# 0002_Page_2.net
KiCad netlist of a schematic drawn in Altium Designer
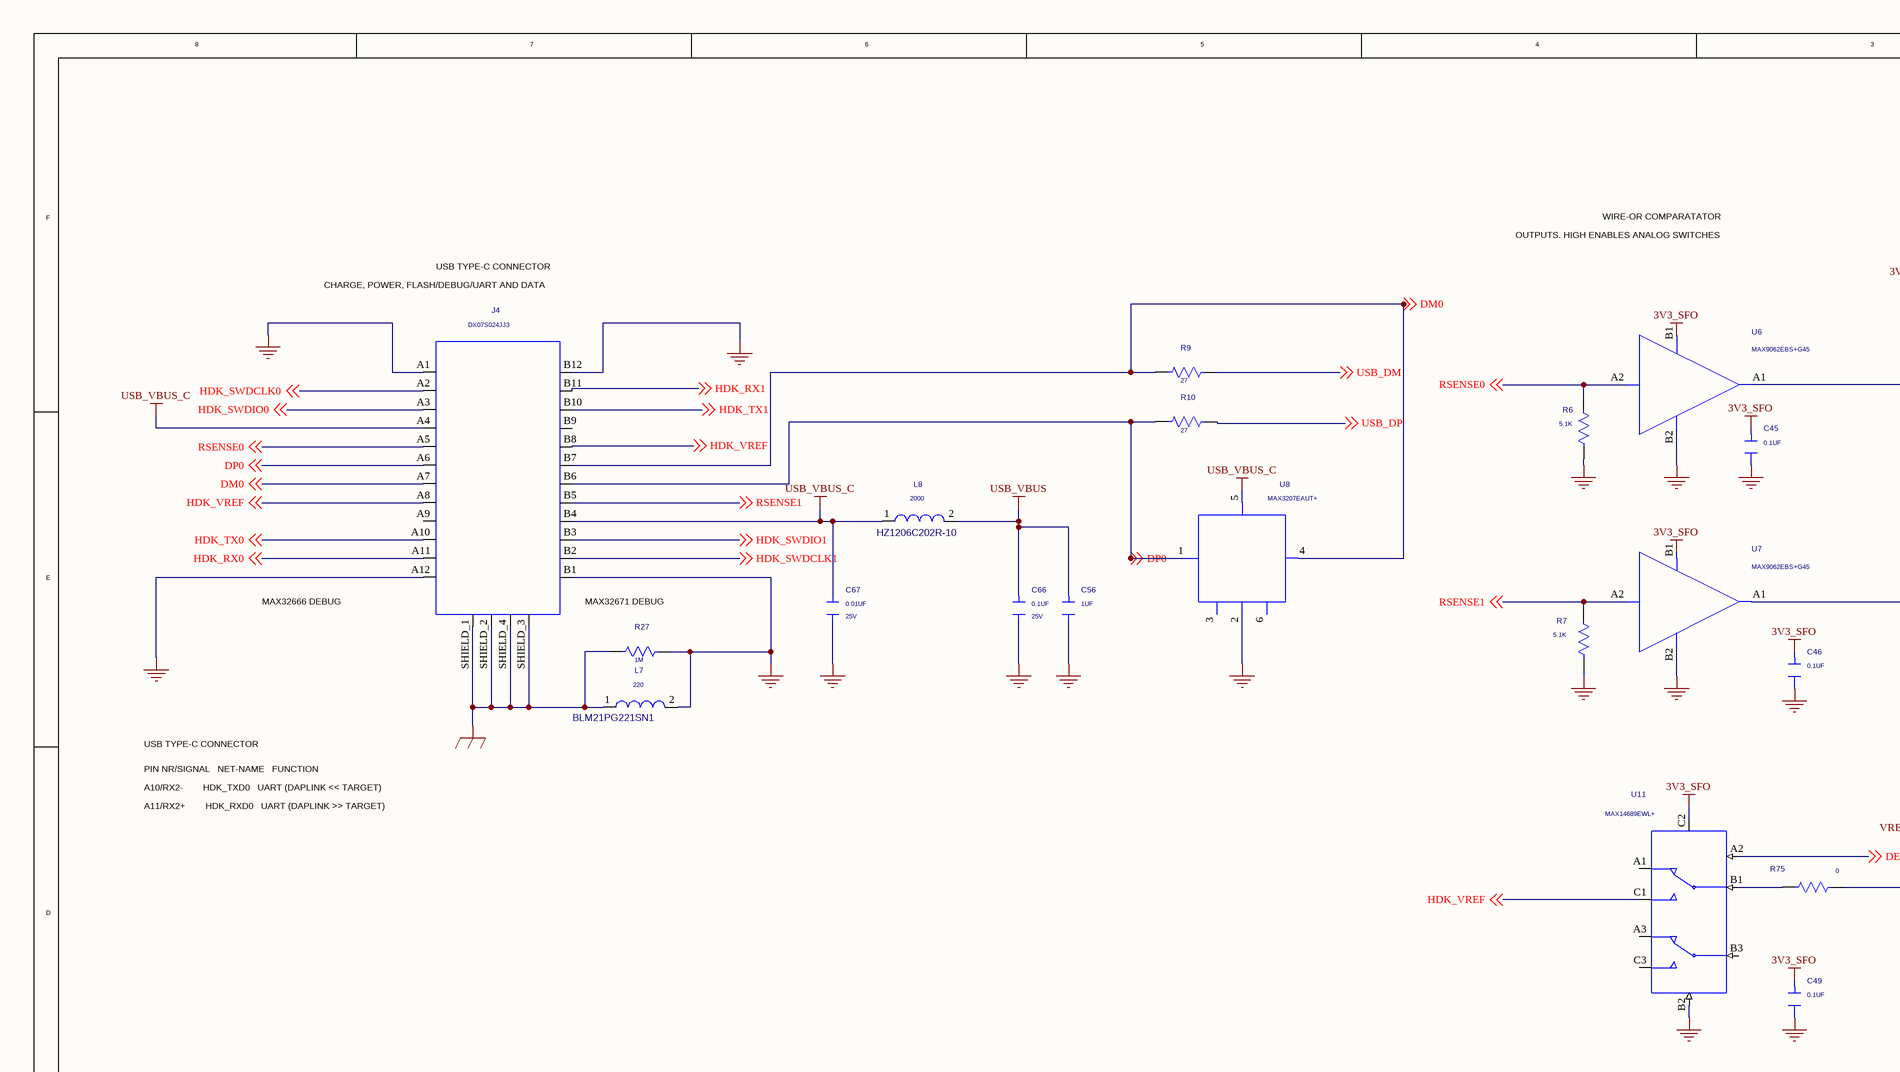
[diagram p0: 0002_Page 2.SchDoc, top left]
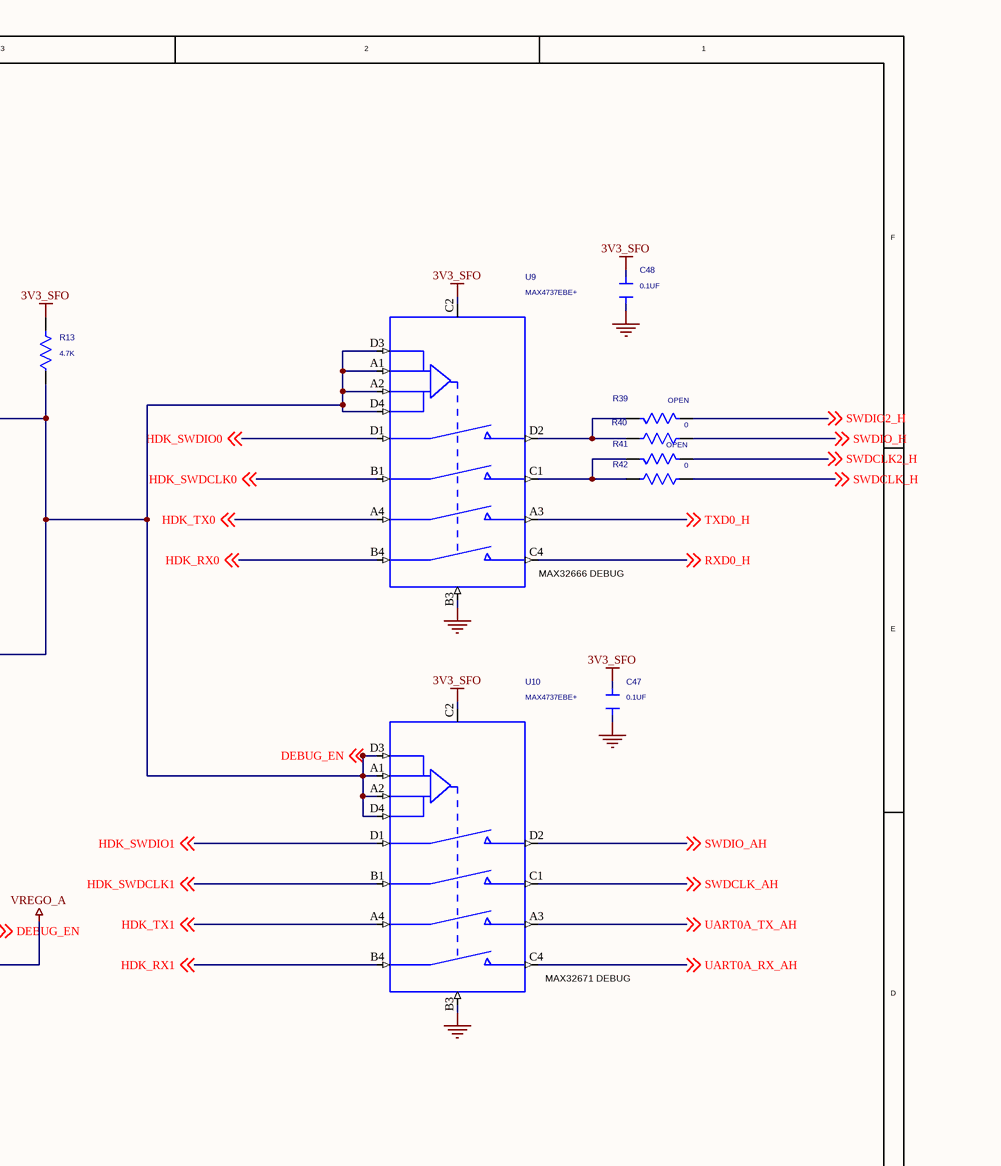
[diagram p1: 0002_Page 2.SchDoc, top middle]
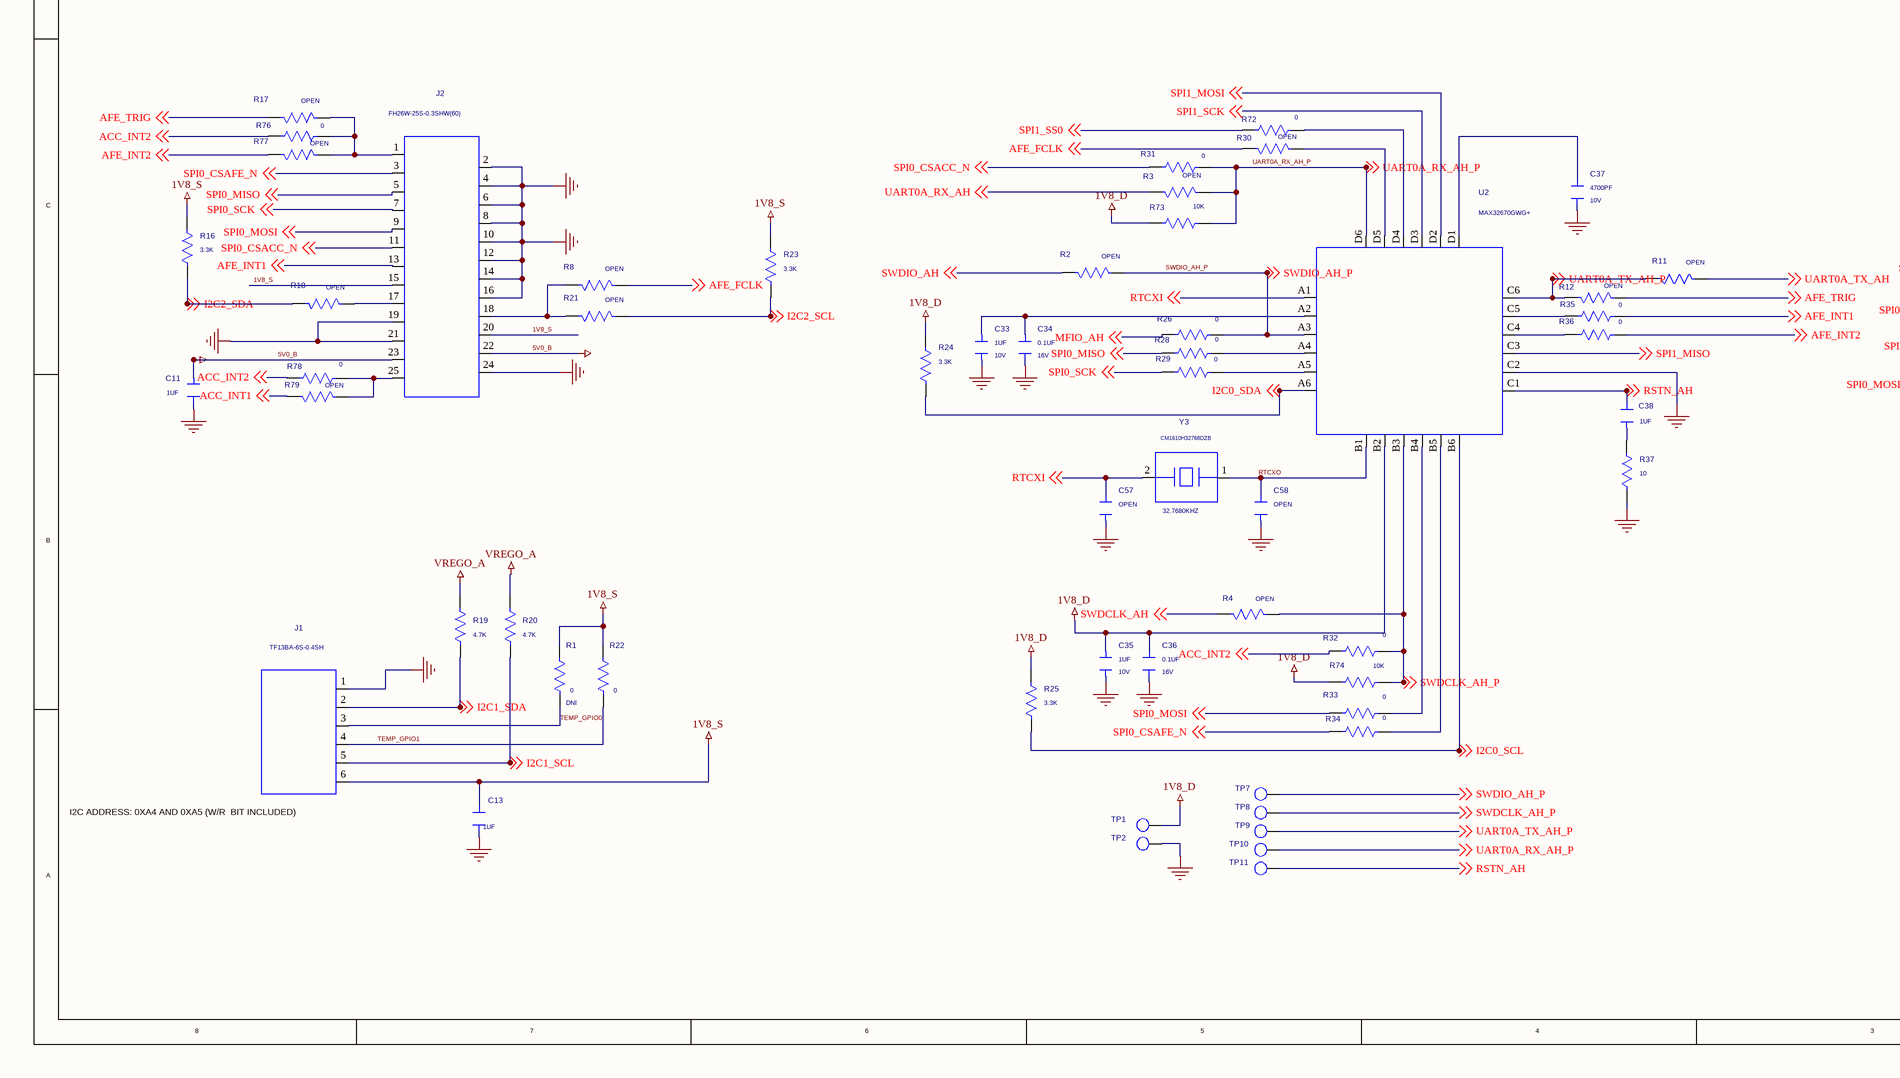
[diagram p2: 0002_Page 2.SchDoc, bottom left]
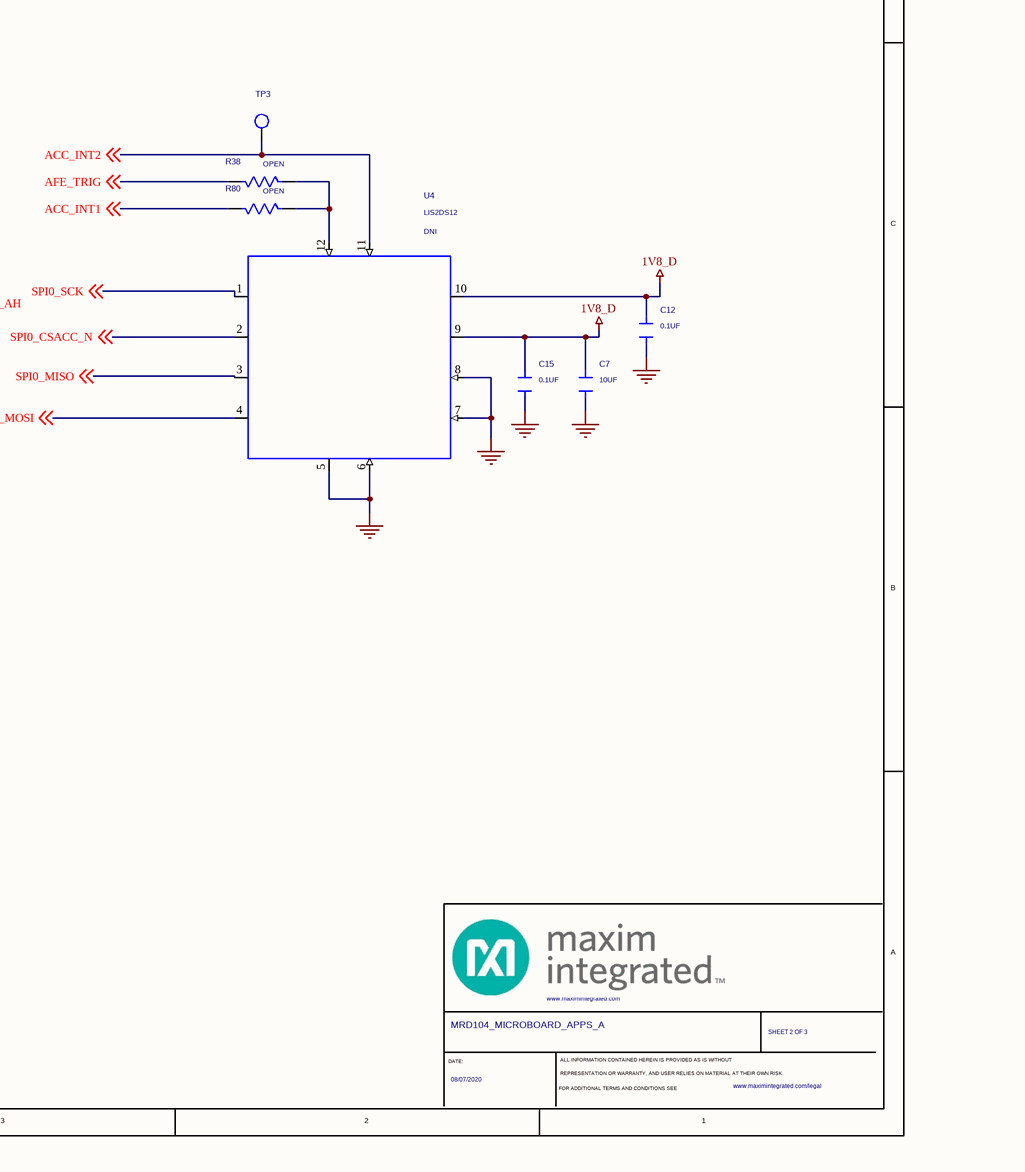
[diagram p3: 0002_Page 2.SchDoc, bottom middle]
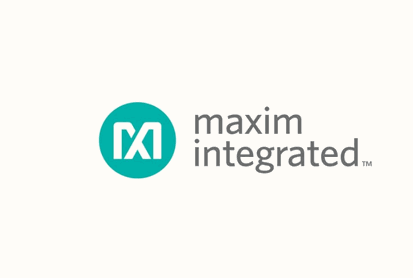
[diagram p4: 0002_Page 2.SchDoc, bottom right]

(export (version "E")
  (design (tool "Eeschema 10.0.6"))
  (components
    (comp (ref "C7")
      (value "10UF")
      (footprint "0603")
      (description "CAP; SMT (0603); 10UF; 20%; 25V; X5R; CERAMIC")
      (fields
        (field (name "MFG_PART_NUMBER") "C1608X5R1E106M080AC;CL10A106MA8NRNC;GRM188R61E106MA73;ZRB18AR61E106ME01;GRT188R61E106ME13")
        (field (name "TOLERANCE") "20%")
      )
      (libsource (lib "*") (part "CAP_NP"))
    )
    (comp (ref "C11")
      (value "1UF")
      (footprint "CAPC0603X33M")
      (description "CAP; SMT (0201); 1UF; 20%; 10V; X5R; CERAMIC")
      (fields (field (name "MFG_PART_NUMBER") "GRM033R61A105ME15") (field (name "TOLERANCE") "20%"))
      (libsource (lib "*") (part "CAP_NP#1"))
    )
    (comp (ref "C12")
      (value "0.1UF")
      (footprint "CAPC0603X33M")
      (description "CAP; SMT (0201); 0.1UF; 10%; 16V; X7S; CERAMIC")
      (fields (field (name "MFG_PART_NUMBER") "GRM033C71C104KE14") (field (name "TOLERANCE") "10%"))
      (libsource (lib "*") (part "CAP_NP"))
    )
    (comp (ref "C13")
      (value "1UF")
      (footprint "CAPC0603X33M")
      (description "CAP; SMT (0201); 1UF; 20%; 10V; X5R; CERAMIC")
      (fields (field (name "MFG_PART_NUMBER") "GRM033R61A105ME15") (field (name "TOLERANCE") "20%"))
      (libsource (lib "*") (part "CAP_NP#1"))
    )
    (comp (ref "C15")
      (value "0.1UF")
      (footprint "CAPC0603X33M")
      (description "CAP; SMT (0201); 0.1UF; 10%; 16V; X7S; CERAMIC")
      (fields (field (name "MFG_PART_NUMBER") "GRM033C71C104KE14") (field (name "TOLERANCE") "10%"))
      (libsource (lib "*") (part "CAP_NP"))
    )
    (comp (ref "C33")
      (value "1UF")
      (footprint "CAPC0603X33M")
      (description "CAP; SMT (0201); 1UF; 20%; 10V; X6S; CERAMIC")
      (fields
        (field (name "MFG_PART_NUMBER") "GRM033C81A105ME05")
        (field (name "TOLERANCE") "20%")
        (field (name "VOLTAGE_RATING") "10V")
      )
      (libsource (lib "*") (part "CAP_NP"))
    )
    (comp (ref "C34")
      (value "0.1UF")
      (footprint "CAPC0603X33M")
      (description "CAP; SMT (0201); 0.1UF; 10%; 16V; X7S; CERAMIC")
      (fields
        (field (name "MFG_PART_NUMBER") "GRM033C71C104KE14")
        (field (name "TOLERANCE") "10%")
        (field (name "VOLTAGE_RATING") "16V")
      )
      (libsource (lib "*") (part "CAP_NP"))
    )
    (comp (ref "C35")
      (value "1UF")
      (footprint "CAPC0603X33M")
      (description "CAP; SMT (0201); 1UF; 20%; 10V; X6S; CERAMIC")
      (fields
        (field (name "MFG_PART_NUMBER") "GRM033C81A105ME05")
        (field (name "TOLERANCE") "20%")
        (field (name "VOLTAGE_RATING") "10V")
      )
      (libsource (lib "*") (part "CAP_NP"))
    )
    (comp (ref "C36")
      (value "0.1UF")
      (footprint "CAPC0603X33M")
      (description "CAP; SMT (0201); 0.1UF; 10%; 16V; X7S; CERAMIC")
      (fields
        (field (name "MFG_PART_NUMBER") "GRM033C71C104KE14")
        (field (name "TOLERANCE") "10%")
        (field (name "VOLTAGE_RATING") "16V")
      )
      (libsource (lib "*") (part "CAP_NP"))
    )
    (comp (ref "C37")
      (value "4700PF")
      (footprint "CAPC0603X33M")
      (description "CAP; SMT (0201); 4700PF; 10%; 10V; X7R; CERAMIC")
      (fields
        (field (name "MFG_PART_NUMBER") "GRM033R71A472KA01D")
        (field (name "TOLERANCE") "10%")
        (field (name "VOLTAGE_RATING") "10V")
      )
      (libsource (lib "*") (part "CAP_NP"))
    )
    (comp (ref "C38")
      (value "1UF")
      (footprint "CAPC0603X33M")
      (description "CAP; SMT (0201); 1UF; 20%; 10V; X6S; CERAMIC")
      (fields (field (name "MFG_PART_NUMBER") "GRM033C81A105ME05") (field (name "TOLERANCE") "20%"))
      (libsource (lib "*") (part "CAP_NP"))
    )
    (comp (ref "C45")
      (value "0.1UF")
      (footprint "CAPC0603X33M")
      (description "CAP; SMT (0201); 0.1UF; 10%; 16V; X5R; CERAMIC")
      (fields
        (field (name "MFG_PART_NUMBER") "GRM033R61C104K;C0603X5R1C104K030BC")
        (field (name "TOLERANCE") "10%")
      )
      (libsource (lib "*") (part "CAP_NP"))
    )
    (comp (ref "C46")
      (value "0.1UF")
      (footprint "CAPC0603X33M")
      (description "CAP; SMT (0201); 0.1UF; 10%; 16V; X5R; CERAMIC")
      (fields
        (field (name "MFG_PART_NUMBER") "GRM033R61C104K;C0603X5R1C104K030BC")
        (field (name "TOLERANCE") "10%")
      )
      (libsource (lib "*") (part "CAP_NP"))
    )
    (comp (ref "C47")
      (value "0.1UF")
      (footprint "CAPC0603X33M")
      (description "CAP; SMT (0201); 0.1UF; 10%; 16V; X5R; CERAMIC")
      (fields
        (field (name "MFG_PART_NUMBER") "GRM033R61C104K;C0603X5R1C104K030BC")
        (field (name "TOLERANCE") "10%")
      )
      (libsource (lib "*") (part "CAP_NP"))
    )
    (comp (ref "C48")
      (value "0.1UF")
      (footprint "CAPC0603X33M")
      (description "CAP; SMT (0201); 0.1UF; 10%; 16V; X5R; CERAMIC")
      (fields
        (field (name "MFG_PART_NUMBER") "GRM033R61C104K;C0603X5R1C104K030BC")
        (field (name "TOLERANCE") "10%")
      )
      (libsource (lib "*") (part "CAP_NP"))
    )
    (comp (ref "C49")
      (value "0.1UF")
      (footprint "CAPC0603X33M")
      (description "CAP; SMT (0201); 0.1UF; 10%; 16V; X5R; CERAMIC")
      (fields
        (field (name "MFG_PART_NUMBER") "GRM033R61C104K;C0603X5R1C104K030BC")
        (field (name "TOLERANCE") "10%")
      )
      (libsource (lib "*") (part "CAP_NP"))
    )
    (comp (ref "C56")
      (value "1UF")
      (footprint "0402")
      (description "CAP; SMT (0402); 1UF; 10%; 35V; X5R;  CERAMIC")
      (fields (field (name "MFG_PART_NUMBER") "C1005X5R1V105K050BC") (field (name "TOLERANCE") "10%"))
      (libsource (lib "*") (part "CAP_NP"))
    )
    (comp (ref "C57")
      (value "OPEN")
      (footprint "CAPC0603X23L")
      (description "CAPACITOR; SMT (0201); OPEN; FORMFACTOR")
      (libsource (lib "*") (part "EK_CAP_NP"))
    )
    (comp (ref "C58")
      (value "OPEN")
      (footprint "CAPC0603X23L")
      (description "CAPACITOR; SMT (0201); OPEN; FORMFACTOR")
      (libsource (lib "*") (part "EK_CAP_NP"))
    )
    (comp (ref "C66")
      (value "0.1UF")
      (footprint "CAPC0603X33M")
      (description "CAP; SMT (0201); 0.1UF; 20%; 25V; X5R; CERAMIC")
      (fields
        (field (name "MFG_PART_NUMBER") "C0603X5R1E104M030BB;GRM033R61E104ME14")
        (field (name "TOLERANCE") "20%")
        (field (name "VOLTAGE_RATING") "25V")
      )
      (libsource (lib "*") (part "CAP_NP"))
    )
    (comp (ref "C67")
      (value "0.01UF")
      (footprint "0402")
      (description "CAP; SMT (0402); 0.01UF; 10%; 25V; X5R; CERAMIC")
      (fields
        (field (name "MFG_PART_NUMBER") "04023D103KAT2A")
        (field (name "TOLERANCE") "10%")
        (field (name "VOLTAGE_RATING") "25V")
      )
      (libsource (lib "*") (part "CAP_NP"))
    )
    (comp (ref "J1")
      (value "TF13BA-6S-0.4SH")
      (footprint "HRSC_TF13BA-6S-0_4SH")
      (description "CONNECTOR; FEMALE; SMT; TF13BA SERIES; FPC/FFC CONNECTOR; 6PINS")
      (fields (field (name "MANUFACTURER") "HIROSE ELECTRIC CO LTD"))
      (libsource (lib "*") (part "TF13BA-6S"))
    )
    (comp (ref "J2")
      (value "FH26W-25S-0.3SHW(60)")
      (footprint "HRSC_FH26W-25S-0_3SHW")
      (description "CONNECTOR; FEMALE; SMT; FPC CONNECTOR; RIGHT ANGLE; 25PINS")
      (fields (field (name "MANUFACTURER") "HIROSE ELECTRIC CO. LTD."))
      (libsource (lib "*") (part "FH26-25S"))
    )
    (comp (ref "J4")
      (value "DX07S024JJ3")
      (footprint "JAE_DX07S024JJ3")
      (description "CONNECTOR; FEMALE; SMT; USB TYPE-C CONNECTOR; DX07 SERIES RECEPTACLE; RIGHT ANGLE; 24PINS")
      (fields
        (field (name "MFG_PART_NUMBER") "DX07S024JJ3R1300")
        (field (name "MANUFACTURER") "JAE ELECTRONIC INDUSTRY")
      )
      (libsource (lib "*") (part "DX07S024JJ3"))
    )
    (comp (ref "L7")
      (value "220")
      (footprint "0805")
      (description "INDUCTOR; SMT (0805); FERRITE-BEAD; 220; TOL=+/-25%; 0.2A")
      (fields
        (field (name "MFG_PART_NUMBER") "BLM21PG221SN1")
        (field (name "TOLERANCE") "25%")
        (field (name "MANUFACTURER") "MURATA")
      )
      (libsource (lib "*") (part "FERRITEBEAD"))
    )
    (comp (ref "L8")
      (value "2000")
      (footprint "1206")
      (description "INDUCTOR; SMT (1206); FERRITE-BEAD; 2000; TOL=+/-25%; 0.3A")
      (fields
        (field (name "MFG_PART_NUMBER") "HZ1206C202R-10")
        (field (name "TOLERANCE") "25%")
        (field (name "MANUFACTURER") "LAIRD TECHNOLOGIES")
      )
      (libsource (lib "*") (part "FERRITEBEAD"))
    )
    (comp (ref "R1")
      (value "0")
      (footprint "RESC0603X33M")
      (description "RES; SMT (0201); 0; 1%; JUMPER; 0.0500W")
      (fields
        (field (name "TOLERANCE") "1%")
        (field (name "VARIANT") "DNI")
        (field (name "MANUFACTURER") "VISHAY DALE;PANASONIC")
      )
      (libsource (lib "*") (part "RES_SMD"))
    )
    (comp (ref "R2")
      (value "OPEN")
      (footprint "RESC0603X23L")
      (description "RESISTOR; 0201; OPEN; FORMFACTOR")
      (libsource (lib "*") (part "EK_RES_SMD"))
    )
    (comp (ref "R3")
      (value "OPEN")
      (footprint "RESC0603X23L")
      (description "RESISTOR; 0201; OPEN; FORMFACTOR")
      (libsource (lib "*") (part "EK_RES_SMD"))
    )
    (comp (ref "R4")
      (value "OPEN")
      (footprint "RESC0603X23L")
      (description "RESISTOR; 0201; OPEN; FORMFACTOR")
      (libsource (lib "*") (part "EK_RES_SMD"))
    )
    (comp (ref "R6")
      (value "5.1K")
      (footprint "RESC0603X33M")
      (description "RES; SMT (0201); 5.1K; 1%; +/-200PPM/DEGC; 0.0500W")
      (fields (field (name "MFG_PART_NUMBER") "ERJ-1GNF5101C") (field (name "TOLERANCE") "1%"))
      (libsource (lib "*") (part "RES_SMD"))
    )
    (comp (ref "R7")
      (value "5.1K")
      (footprint "RESC0603X33M")
      (description "RES; SMT (0201); 5.1K; 1%; +/-200PPM/DEGC; 0.0500W")
      (fields (field (name "MFG_PART_NUMBER") "ERJ-1GNF5101C") (field (name "TOLERANCE") "1%"))
      (libsource (lib "*") (part "RES_SMD"))
    )
    (comp (ref "R8")
      (value "OPEN")
      (footprint "RESC0603X23L")
      (description "RESISTOR; 0201; OPEN; FORMFACTOR")
      (libsource (lib "*") (part "EK_RES_SMD"))
    )
    (comp (ref "R9")
      (value "27")
      (footprint "RESC0603X33M")
      (description "RES; SMT (0201); 27; 1%; +/-100PPM/DEGC; 0.0500W")
      (fields (field (name "MFG_PART_NUMBER") "ERJ-1GEF27R0C") (field (name "TOLERANCE") "1%"))
      (libsource (lib "*") (part "RES_SMD"))
    )
    (comp (ref "R10")
      (value "27")
      (footprint "RESC0603X33M")
      (description "RES; SMT (0201); 27; 1%; +/-100PPM/DEGC; 0.0500W")
      (fields (field (name "MFG_PART_NUMBER") "ERJ-1GEF27R0C") (field (name "TOLERANCE") "1%"))
      (libsource (lib "*") (part "RES_SMD"))
    )
    (comp (ref "R11")
      (value "OPEN")
      (footprint "RESC0603X23L")
      (description "RESISTOR; 0201; OPEN; FORMFACTOR")
      (libsource (lib "*") (part "EK_RES_SMD"))
    )
    (comp (ref "R12")
      (value "OPEN")
      (footprint "RESC0603X23L")
      (description "RESISTOR; 0201; OPEN; FORMFACTOR")
      (libsource (lib "*") (part "EK_RES_SMD"))
    )
    (comp (ref "R13")
      (value "4.7K")
      (footprint "RESC0603X26M")
      (description "RES; SMT (0201); 4.7K; 1%; +/-200PPM/DEGC; 0.0500W")
      (fields (field (name "MFG_PART_NUMBER") "ERJ-1GNF4701") (field (name "TOLERANCE") "1%"))
      (libsource (lib "*") (part "RES_SMD#1"))
    )
    (comp (ref "R16")
      (value "3.3K")
      (footprint "RESC0603X33M")
      (description "RES; SMT (0201); 3.3K; 1%; +/-100PPM/DEGC; 0.0500W")
      (fields (field (name "MFG_PART_NUMBER") "ERJ-1GEF3301C") (field (name "TOLERANCE") "1%"))
      (libsource (lib "*") (part "RES_SMD"))
    )
    (comp (ref "R17")
      (value "OPEN")
      (footprint "RESC0603X23L")
      (description "RESISTOR; 0201; OPEN; FORMFACTOR")
      (libsource (lib "*") (part "EK_RES_SMD"))
    )
    (comp (ref "R18")
      (value "OPEN")
      (footprint "RESC0603X23L")
      (description "RESISTOR; 0201; OPEN; FORMFACTOR")
      (libsource (lib "*") (part "EK_RES_SMD"))
    )
    (comp (ref "R19")
      (value "4.7K")
      (footprint "RESC0603X26M")
      (description "RES; SMT (0201); 4.7K; 1%; +/-200PPM/DEGC; 0.0500W")
      (fields (field (name "MFG_PART_NUMBER") "ERJ-1GNF4701") (field (name "TOLERANCE") "1%"))
      (libsource (lib "*") (part "RES_SMD"))
    )
    (comp (ref "R20")
      (value "4.7K")
      (footprint "RESC0603X26M")
      (description "RES; SMT (0201); 4.7K; 1%; +/-200PPM/DEGC; 0.0500W")
      (fields (field (name "MFG_PART_NUMBER") "ERJ-1GNF4701") (field (name "TOLERANCE") "1%"))
      (libsource (lib "*") (part "RES_SMD"))
    )
    (comp (ref "R21")
      (value "OPEN")
      (footprint "RESC0603X23L")
      (description "RESISTOR; 0201; OPEN; FORMFACTOR")
      (libsource (lib "*") (part "EK_RES_SMD"))
    )
    (comp (ref "R22")
      (value "0")
      (footprint "RESC0603X33M")
      (description "RES; SMT (0201); 0; 1%; JUMPER; 0.0500W")
      (fields (field (name "TOLERANCE") "1%") (field (name "MANUFACTURER") "VISHAY DALE;PANASONIC"))
      (libsource (lib "*") (part "RES_SMD"))
    )
    (comp (ref "R23")
      (value "3.3K")
      (footprint "RESC0603X33M")
      (description "RES; SMT (0201); 3.3K; 1%; +/-100PPM/DEGC; 0.0500W")
      (fields (field (name "MFG_PART_NUMBER") "ERJ-1GEF3301C") (field (name "TOLERANCE") "1%"))
      (libsource (lib "*") (part "RES_SMD"))
    )
    (comp (ref "R24")
      (value "3.3K")
      (footprint "RESC0603X33M")
      (description "RES; SMT (0201); 3.3K; 1%; +/-100PPM/DEGC; 0.0500W")
      (fields (field (name "MFG_PART_NUMBER") "ERJ-1GEF3301C") (field (name "TOLERANCE") "1%"))
      (libsource (lib "*") (part "RES_SMD"))
    )
    (comp (ref "R25")
      (value "3.3K")
      (footprint "RESC0603X33M")
      (description "RES; SMT (0201); 3.3K; 1%; +/-100PPM/DEGC; 0.0500W")
      (fields (field (name "MFG_PART_NUMBER") "ERJ-1GEF3301C") (field (name "TOLERANCE") "1%"))
      (libsource (lib "*") (part "RES_SMD"))
    )
    (comp (ref "R26")
      (value "0")
      (footprint "RESC0603X33M")
      (description "RES; SMT (0201); 0; 1%; JUMPER; 0.0500W")
      (fields (field (name "TOLERANCE") "1%") (field (name "MANUFACTURER") "VISHAY DALE;PANASONIC"))
      (libsource (lib "*") (part "RES_SMD"))
    )
    (comp (ref "R27")
      (value "1M")
      (footprint "0402")
      (description "RES; SMT (0402); 1M; 1%; +/-100PPM/DEGC; 0.1000W")
      (fields (field (name "MFG_PART_NUMBER") "ERJ-2RKF1004") (field (name "TOLERANCE") "1%"))
      (libsource (lib "*") (part "RES_SMD"))
    )
    (comp (ref "R28")
      (value "0")
      (footprint "RESC0603X33M")
      (description "RES; SMT (0201); 0; 1%; JUMPER; 0.0500W")
      (fields (field (name "TOLERANCE") "1%") (field (name "MANUFACTURER") "VISHAY DALE;PANASONIC"))
      (libsource (lib "*") (part "RES_SMD"))
    )
    (comp (ref "R29")
      (value "0")
      (footprint "RESC0603X33M")
      (description "RES; SMT (0201); 0; 1%; JUMPER; 0.0500W")
      (fields (field (name "TOLERANCE") "1%") (field (name "MANUFACTURER") "VISHAY DALE;PANASONIC"))
      (libsource (lib "*") (part "RES_SMD"))
    )
    (comp (ref "R30")
      (value "OPEN")
      (footprint "RESC0603X23L")
      (description "RESISTOR; 0201; OPEN; FORMFACTOR")
      (libsource (lib "*") (part "EK_RES_SMD"))
    )
    (comp (ref "R31")
      (value "0")
      (footprint "RESC0603X33M")
      (description "RES; SMT (0201); 0; 1%; JUMPER; 0.0500W")
      (fields (field (name "TOLERANCE") "1%") (field (name "MANUFACTURER") "VISHAY DALE;PANASONIC"))
      (libsource (lib "*") (part "RES_SMD"))
    )
    (comp (ref "R32")
      (value "0")
      (footprint "RESC0603X33M")
      (description "RES; SMT (0201); 0; 1%; JUMPER; 0.0500W")
      (fields (field (name "TOLERANCE") "1%") (field (name "MANUFACTURER") "VISHAY DALE;PANASONIC"))
      (libsource (lib "*") (part "RES_SMD"))
    )
    (comp (ref "R33")
      (value "0")
      (footprint "RESC0603X33M")
      (description "RES; SMT (0201); 0; 1%; JUMPER; 0.0500W")
      (fields (field (name "TOLERANCE") "1%") (field (name "MANUFACTURER") "VISHAY DALE;PANASONIC"))
      (libsource (lib "*") (part "RES_SMD"))
    )
    (comp (ref "R34")
      (value "0")
      (footprint "RESC0603X33M")
      (description "RES; SMT (0201); 0; 1%; JUMPER; 0.0500W")
      (fields (field (name "TOLERANCE") "1%") (field (name "MANUFACTURER") "VISHAY DALE;PANASONIC"))
      (libsource (lib "*") (part "RES_SMD"))
    )
    (comp (ref "R35")
      (value "0")
      (footprint "RESC0603X33M")
      (description "RES; SMT (0201); 0; 1%; JUMPER; 0.0500W")
      (fields (field (name "TOLERANCE") "1%") (field (name "MANUFACTURER") "VISHAY DALE;PANASONIC"))
      (libsource (lib "*") (part "RES_SMD"))
    )
    (comp (ref "R36")
      (value "0")
      (footprint "RESC0603X33M")
      (description "RES; SMT (0201); 0; 1%; JUMPER; 0.0500W")
      (fields (field (name "TOLERANCE") "1%") (field (name "MANUFACTURER") "VISHAY DALE;PANASONIC"))
      (libsource (lib "*") (part "RES_SMD"))
    )
    (comp (ref "R37")
      (value "10")
      (footprint "RESC0603X33M")
      (description "RES; SMT (0201); 10; 1%; +/-100PPM/DEGC; 0.0500W")
      (fields (field (name "MFG_PART_NUMBER") "ERJ-1GEF10R0") (field (name "TOLERANCE") "1%"))
      (libsource (lib "*") (part "RES_SMD"))
    )
    (comp (ref "R38")
      (value "OPEN")
      (footprint "RESC0603X23L")
      (description "RESISTOR; 0201; OPEN; FORMFACTOR")
      (libsource (lib "*") (part "EK_RES_SMD"))
    )
    (comp (ref "R39")
      (value "OPEN")
      (footprint "RESC0603X23L")
      (description "RESISTOR; 0201; OPEN; FORMFACTOR")
      (libsource (lib "*") (part "EK_RES_SMD"))
    )
    (comp (ref "R40")
      (value "0")
      (footprint "RESC0603X33M")
      (description "RES; SMT (0201); 0; 1%; JUMPER; 0.0500W")
      (fields (field (name "TOLERANCE") "1%") (field (name "MANUFACTURER") "VISHAY DALE;PANASONIC"))
      (libsource (lib "*") (part "RES_SMD"))
    )
    (comp (ref "R41")
      (value "OPEN")
      (footprint "RESC0603X23L")
      (description "RESISTOR; 0201; OPEN; FORMFACTOR")
      (libsource (lib "*") (part "EK_RES_SMD"))
    )
    (comp (ref "R42")
      (value "0")
      (footprint "RESC0603X33M")
      (description "RES; SMT (0201); 0; 1%; JUMPER; 0.0500W")
      (fields (field (name "TOLERANCE") "1%") (field (name "MANUFACTURER") "VISHAY DALE;PANASONIC"))
      (libsource (lib "*") (part "RES_SMD"))
    )
    (comp (ref "R72")
      (value "0")
      (footprint "RESC0603X33M")
      (description "RES; SMT (0201); 0; 1%; JUMPER; 0.0500W")
      (fields (field (name "TOLERANCE") "1%") (field (name "MANUFACTURER") "VISHAY DALE;PANASONIC"))
      (libsource (lib "*") (part "RES_SMD"))
    )
    (comp (ref "R73")
      (value "10K")
      (footprint "RESC0603X33M")
      (description "RES; SMT (0201); 10K; 5%; +/-200PPM/DEGC; 0.0500W")
      (fields (field (name "MFG_PART_NUMBER") "ERJ-1GNJ103") (field (name "TOLERANCE") "5%"))
      (libsource (lib "*") (part "RES_SMD"))
    )
    (comp (ref "R74")
      (value "10K")
      (footprint "RESC0603X33M")
      (description "RES; SMT (0201); 10K; 5%; +/-200PPM/DEGC; 0.0500W")
      (fields (field (name "MFG_PART_NUMBER") "ERJ-1GNJ103") (field (name "TOLERANCE") "5%"))
      (libsource (lib "*") (part "RES_SMD"))
    )
    (comp (ref "R75")
      (value "0")
      (footprint "RESC0603X33M")
      (description "RES; SMT (0201); 0; 1%; JUMPER; 0.0500W")
      (fields (field (name "TOLERANCE") "1%") (field (name "MANUFACTURER") "VISHAY DALE;PANASONIC"))
      (libsource (lib "*") (part "RES_SMD"))
    )
    (comp (ref "R76")
      (value "0")
      (footprint "RESC0603X33M")
      (description "RES; SMT (0201); 0; 1%; JUMPER; 0.0500W")
      (fields (field (name "TOLERANCE") "1%") (field (name "MANUFACTURER") "VISHAY DALE;PANASONIC"))
      (libsource (lib "*") (part "RES_SMD"))
    )
    (comp (ref "R77")
      (value "OPEN")
      (footprint "RESC0603X23L")
      (description "RESISTOR; 0201; OPEN; FORMFACTOR")
      (libsource (lib "*") (part "EK_RES_SMD"))
    )
    (comp (ref "R78")
      (value "0")
      (footprint "RESC0603X33M")
      (description "RES; SMT (0201); 0; 1%; JUMPER; 0.0500W")
      (fields (field (name "TOLERANCE") "1%") (field (name "MANUFACTURER") "VISHAY DALE;PANASONIC"))
      (libsource (lib "*") (part "RES_SMD"))
    )
    (comp (ref "R79")
      (value "OPEN")
      (footprint "RESC0603X23L")
      (description "RESISTOR; 0201; OPEN; FORMFACTOR")
      (libsource (lib "*") (part "EK_RES_SMD"))
    )
    (comp (ref "R80")
      (value "OPEN")
      (footprint "RESC0603X23L")
      (description "RESISTOR; 0201; OPEN; FORMFACTOR")
      (libsource (lib "*") (part "EK_RES_SMD"))
    )
    (comp (ref "TP1")
      (value "TP14PAD")
      (footprint "TP_CIR_0-3556")
      (description "TEST POINT; PAD DIA=0.014IN (0.3556MM)")
      (libsource (lib "*") (part "EVKIT_TP"))
    )
    (comp (ref "TP2")
      (value "TP14PAD")
      (footprint "TP_CIR_0-3556")
      (description "TEST POINT; PAD DIA=0.014IN (0.3556MM)")
      (libsource (lib "*") (part "EVKIT_TP"))
    )
    (comp (ref "TP3")
      (value "TP14PAD")
      (footprint "TP_CIR_0-3556")
      (description "TEST POINT; PAD DIA=0.014IN (0.3556MM)")
      (libsource (lib "*") (part "EVKIT_TP"))
    )
    (comp (ref "TP7")
      (value "TP14PAD")
      (footprint "TP_CIR_0-3556")
      (description "TEST POINT; PAD DIA=0.014IN (0.3556MM)")
      (libsource (lib "*") (part "EVKIT_TP"))
    )
    (comp (ref "TP8")
      (value "TP14PAD")
      (footprint "TP_CIR_0-3556")
      (description "TEST POINT; PAD DIA=0.014IN (0.3556MM)")
      (libsource (lib "*") (part "EVKIT_TP"))
    )
    (comp (ref "TP9")
      (value "TP14PAD")
      (footprint "TP_CIR_0-3556")
      (description "TEST POINT; PAD DIA=0.014IN (0.3556MM)")
      (libsource (lib "*") (part "EVKIT_TP"))
    )
    (comp (ref "TP10")
      (value "TP14PAD")
      (footprint "TP_CIR_0-3556")
      (description "TEST POINT; PAD DIA=0.014IN (0.3556MM)")
      (libsource (lib "*") (part "EVKIT_TP"))
    )
    (comp (ref "TP11")
      (value "TP14PAD")
      (footprint "TP_CIR_0-3556")
      (description "TEST POINT; PAD DIA=0.014IN (0.3556MM)")
      (libsource (lib "*") (part "EVKIT_TP"))
    )
    (comp (ref "U2")
      (value "MAX32670GWG+")
      (footprint "MAXIM_21-100511")
      (description "EVKIT PART - IC; MAX32670GWG+; PACKAGE OUTLINE DRAWING: 21-100151; PACKAGE CODE: W241H2+1; WLP24")
      (fields (field (name "MANUFACTURER") "MAXIM"))
      (libsource (lib "*") (part "EK_MAX32670"))
    )
    (comp (ref "U4")
      (value "LIS2DS12")
      (footprint "STMC_LGA-12")
      (fields (field (name "VARIANT") "DNI") (field (name "MANUFACTURER") "ST MICROELECTRONICS"))
      (libsource (lib "*") (part "LIS2DS12"))
    )
    (comp (ref "U6")
      (value "MAX9062EBS+G45")
      (footprint "MAXIM_21-0789")
      (description "IC; COMP; ULTRA-SMALL; LOW-POWER SINGLE COMPARATOR; UCSP4")
      (fields (field (name "MANUFACTURER") "MAXIM"))
      (libsource (lib "*") (part "MAX9062"))
    )
    (comp (ref "U7")
      (value "MAX9062EBS+G45")
      (footprint "MAXIM_21-0789")
      (description "IC; COMP; ULTRA-SMALL; LOW-POWER SINGLE COMPARATOR; UCSP4")
      (fields (field (name "MANUFACTURER") "MAXIM"))
      (libsource (lib "*") (part "MAX9062"))
    )
    (comp (ref "U8")
      (value "MAX3207EAUT+")
      (footprint "MAXIM_90-0175")
      (description "IC; PROT; DUAL, QUAD, AND HEX HIGH-SPEED DIFFERENTIAL ESD-PROTECTION IC; SOT23-6")
      (fields (field (name "MANUFACTURER") "MAXIM"))
      (libsource (lib "*") (part "MAX3207"))
    )
    (comp (ref "U9")
      (value "MAX4737EBE+")
      (footprint "MAXIM_21-0101_B16-4")
      (description "IC; ASW; 4.5OHM QUAD SPST ANALOG SWITCH IN UCSP; 2X2; UCSP16")
      (fields (field (name "MANUFACTURER") "MAXIM"))
      (libsource (lib "*") (part "MAX4737"))
    )
    (comp (ref "U10")
      (value "MAX4737EBE+")
      (footprint "MAXIM_21-0101_B16-4")
      (description "IC; ASW; 4.5OHM QUAD SPST ANALOG SWITCH IN UCSP; 2X2; UCSP16")
      (fields (field (name "MANUFACTURER") "MAXIM"))
      (libsource (lib "*") (part "MAX4737"))
    )
    (comp (ref "U11")
      (value "MAX14689EWL+")
      (footprint "MAXIM_21-0459_W91B1-7")
      (description "IC; ASW; ULTRA-SMALL LOW-RON BEYOND-THE-RAILS DPDT ANALOG SWITCHES; WLP9")
      (fields (field (name "MANUFACTURER") "MAXIM"))
      (libsource (lib "*") (part "MAX14689"))
    )
    (comp (ref "Y3")
      (value "32.7680KHZ")
      (footprint "XTALDFN160X100X50-2M")
      (description "CRYSTAL; SMT; 32.7680KHZ; 6PF; TOL = +/-20PPM")
      (fields
        (field (name "MFG_PART_NUMBER") "CM1610H32768DZB")
        (field (name "TOLERANCE") "+/-20PPM")
        (field (name "MANUFACTURER") "CITIZEN")
      )
      (libsource (lib "*") (part "XTAL"))
    )
  )
  (nets
    (net (code "1") (name "/RTCXO") (class "Default")
      (node (ref "C58") (pin "2") (pinfunction "2_2") (pintype "bidirectional"))
      (node (ref "U2") (pin "B1") (pinfunction "B1_B1") (pintype "bidirectional"))
      (node (ref "Y3") (pin "1") (pinfunction "1_1") (pintype "bidirectional"))
    )
    (net (code "2") (name "/TEMP_GPIO0") (class "Default")
      (node (ref "J1") (pin "3") (pinfunction "3_3") (pintype "bidirectional"))
      (node (ref "R1") (pin "1") (pinfunction "1_1") (pintype "bidirectional"))
    )
    (net (code "3") (name "/TEMP_GPIO1") (class "Default")
      (node (ref "J1") (pin "4") (pinfunction "4_4") (pintype "bidirectional"))
      (node (ref "R22") (pin "1") (pinfunction "1_1") (pintype "bidirectional"))
    )
    (net (code "4") (name "1V8_D") (class "Default")
      (node (ref "C12") (pin "2") (pinfunction "2_2") (pintype "bidirectional"))
      (node (ref "C15") (pin "2") (pinfunction "2_2") (pintype "bidirectional"))
      (node (ref "C35") (pin "2") (pinfunction "2_2") (pintype "bidirectional"))
      (node (ref "C36") (pin "2") (pinfunction "2_2") (pintype "bidirectional"))
      (node (ref "C7") (pin "2") (pinfunction "2_2") (pintype "bidirectional"))
      (node (ref "R24") (pin "2") (pinfunction "2_2") (pintype "bidirectional"))
      (node (ref "R25") (pin "2") (pinfunction "2_2") (pintype "bidirectional"))
      (node (ref "R73") (pin "1") (pinfunction "1_1") (pintype "bidirectional"))
      (node (ref "R74") (pin "1") (pinfunction "1_1") (pintype "bidirectional"))
      (node (ref "TP1") (pin "1") (pinfunction "TP1_1") (pintype "bidirectional"))
      (node (ref "U2") (pin "B2") (pinfunction "B2_B2") (pintype "bidirectional"))
      (node (ref "U4") (pin "10") (pinfunction "VDDIO_10") (pintype "bidirectional"))
      (node (ref "U4") (pin "9") (pinfunction "VDD_9") (pintype "bidirectional"))
    )
    (net (code "5") (name "1V8_S") (class "Default")
      (node (ref "C13") (pin "2") (pinfunction "2_2") (pintype "bidirectional"))
      (node (ref "J1") (pin "6") (pinfunction "6_6") (pintype "bidirectional"))
      (node (ref "J2") (pin "15") (pinfunction "15_15") (pintype "bidirectional"))
      (node (ref "J2") (pin "20") (pinfunction "20_20") (pintype "bidirectional"))
      (node (ref "R1") (pin "2") (pinfunction "2_2") (pintype "bidirectional"))
      (node (ref "R16") (pin "2") (pinfunction "2_2") (pintype "bidirectional"))
      (node (ref "R22") (pin "2") (pinfunction "2_2") (pintype "bidirectional"))
      (node (ref "R23") (pin "2") (pinfunction "2_2") (pintype "bidirectional"))
    )
    (net (code "6") (name "3V3_SFO") (class "Default")
      (node (ref "C45") (pin "2") (pinfunction "2_2") (pintype "bidirectional"))
      (node (ref "C46") (pin "2") (pinfunction "2_2") (pintype "bidirectional"))
      (node (ref "C47") (pin "2") (pinfunction "2_2") (pintype "bidirectional"))
      (node (ref "C48") (pin "2") (pinfunction "2_2") (pintype "bidirectional"))
      (node (ref "C49") (pin "2") (pinfunction "2_2") (pintype "bidirectional"))
      (node (ref "R13") (pin "1") (pinfunction "1_1") (pintype "bidirectional"))
      (node (ref "U10") (pin "C2") (pinfunction "V+_C2") (pintype "bidirectional"))
      (node (ref "U11") (pin "C2") (pinfunction "VCC_C2") (pintype "bidirectional"))
      (node (ref "U6") (pin "B1") (pinfunction "VCC_B1") (pintype "bidirectional"))
      (node (ref "U7") (pin "B1") (pinfunction "VCC_B1") (pintype "bidirectional"))
      (node (ref "U9") (pin "C2") (pinfunction "V+_C2") (pintype "bidirectional"))
    )
    (net (code "7") (name "5V0_B") (class "Default")
      (node (ref "C11") (pin "2") (pinfunction "2_2") (pintype "bidirectional"))
      (node (ref "J2") (pin "22") (pinfunction "22_22") (pintype "bidirectional"))
      (node (ref "J2") (pin "23") (pinfunction "23_23") (pintype "bidirectional"))
    )
    (net (code "8") (name "ACC_INT1") (class "Default")
      (node (ref "R79") (pin "2") (pinfunction "2_2") (pintype "bidirectional"))
      (node (ref "R80") (pin "2") (pinfunction "2_2") (pintype "bidirectional"))
    )
    (net (code "9") (name "ACC_INT2") (class "Default")
      (node (ref "R32") (pin "1") (pinfunction "1_1") (pintype "bidirectional"))
      (node (ref "R76") (pin "1") (pinfunction "1_1") (pintype "bidirectional"))
      (node (ref "R78") (pin "1") (pinfunction "1_1") (pintype "bidirectional"))
      (node (ref "TP3") (pin "1") (pinfunction "TP1_1") (pintype "bidirectional"))
      (node (ref "U4") (pin "11") (pinfunction "INT2_11") (pintype "input"))
    )
    (net (code "10") (name "AFE_FCLK") (class "Default")
      (node (ref "R30") (pin "2") (pinfunction "2_2") (pintype "bidirectional"))
      (node (ref "R8") (pin "1") (pinfunction "1_1") (pintype "bidirectional"))
    )
    (net (code "11") (name "AFE_INT1") (class "Default")
      (node (ref "J2") (pin "13") (pinfunction "13_13") (pintype "bidirectional"))
      (node (ref "R35") (pin "2") (pinfunction "2_2") (pintype "bidirectional"))
    )
    (net (code "12") (name "AFE_INT2") (class "Default")
      (node (ref "R36") (pin "2") (pinfunction "2_2") (pintype "bidirectional"))
      (node (ref "R77") (pin "2") (pinfunction "2_2") (pintype "bidirectional"))
    )
    (net (code "13") (name "AFE_TRIG") (class "Default")
      (node (ref "R12") (pin "1") (pinfunction "1_1") (pintype "bidirectional"))
      (node (ref "R17") (pin "2") (pinfunction "2_2") (pintype "bidirectional"))
      (node (ref "R38") (pin "2") (pinfunction "2_2") (pintype "bidirectional"))
    )
    (net (code "14") (name "DEBUG_EN") (class "Default")
      (node (ref "R13") (pin "2") (pinfunction "2_2") (pintype "bidirectional"))
      (node (ref "U10") (pin "A1") (pinfunction "IN2_A1") (pintype "input"))
      (node (ref "U10") (pin "A2") (pinfunction "IN3_A2") (pintype "input"))
      (node (ref "U10") (pin "D3") (pinfunction "IN1_D3") (pintype "input"))
      (node (ref "U10") (pin "D4") (pinfunction "IN4_D4") (pintype "input"))
      (node (ref "U11") (pin "A2") (pinfunction "CB_A2") (pintype "input"))
      (node (ref "U6") (pin "A1") (pinfunction "OUT_A1") (pintype "output"))
      (node (ref "U7") (pin "A1") (pinfunction "OUT_A1") (pintype "output"))
      (node (ref "U9") (pin "A1") (pinfunction "IN2_A1") (pintype "input"))
      (node (ref "U9") (pin "A2") (pinfunction "IN3_A2") (pintype "input"))
      (node (ref "U9") (pin "D3") (pinfunction "IN1_D3") (pintype "input"))
      (node (ref "U9") (pin "D4") (pinfunction "IN4_D4") (pintype "input"))
    )
    (net (code "15") (name "DM0") (class "Default")
      (node (ref "J4") (pin "A7") (pinfunction "A7_A7") (pintype "bidirectional"))
      (node (ref "J4") (pin "B7") (pinfunction "B7_B7") (pintype "bidirectional"))
      (node (ref "R9") (pin "1") (pinfunction "1_1") (pintype "bidirectional"))
      (node (ref "U8") (pin "4") (pinfunction "I/O_2_4") (pintype "bidirectional"))
    )
    (net (code "16") (name "DP0") (class "Default")
      (node (ref "J4") (pin "A6") (pinfunction "A6_A6") (pintype "bidirectional"))
      (node (ref "J4") (pin "B6") (pinfunction "B6_B6") (pintype "bidirectional"))
      (node (ref "R10") (pin "1") (pinfunction "1_1") (pintype "bidirectional"))
      (node (ref "U8") (pin "1") (pinfunction "I/O_1_1") (pintype "bidirectional"))
    )
    (net (code "17") (name "GND_POWER") (class "Default")
      (node (ref "C11") (pin "1") (pinfunction "1_1") (pintype "bidirectional"))
      (node (ref "C12") (pin "1") (pinfunction "1_1") (pintype "bidirectional"))
      (node (ref "C13") (pin "1") (pinfunction "1_1") (pintype "bidirectional"))
      (node (ref "C15") (pin "1") (pinfunction "1_1") (pintype "bidirectional"))
      (node (ref "C33") (pin "1") (pinfunction "1_1") (pintype "bidirectional"))
      (node (ref "C34") (pin "1") (pinfunction "1_1") (pintype "bidirectional"))
      (node (ref "C35") (pin "1") (pinfunction "1_1") (pintype "bidirectional"))
      (node (ref "C36") (pin "1") (pinfunction "1_1") (pintype "bidirectional"))
      (node (ref "C37") (pin "1") (pinfunction "1_1") (pintype "bidirectional"))
      (node (ref "C45") (pin "1") (pinfunction "1_1") (pintype "bidirectional"))
      (node (ref "C46") (pin "1") (pinfunction "1_1") (pintype "bidirectional"))
      (node (ref "C47") (pin "1") (pinfunction "1_1") (pintype "bidirectional"))
      (node (ref "C48") (pin "1") (pinfunction "1_1") (pintype "bidirectional"))
      (node (ref "C49") (pin "1") (pinfunction "1_1") (pintype "bidirectional"))
      (node (ref "C56") (pin "1") (pinfunction "1_1") (pintype "bidirectional"))
      (node (ref "C57") (pin "1") (pinfunction "1_1") (pintype "bidirectional"))
      (node (ref "C58") (pin "1") (pinfunction "1_1") (pintype "bidirectional"))
      (node (ref "C66") (pin "1") (pinfunction "1_1") (pintype "bidirectional"))
      (node (ref "C67") (pin "1") (pinfunction "1_1") (pintype "bidirectional"))
      (node (ref "C7") (pin "1") (pinfunction "1_1") (pintype "bidirectional"))
      (node (ref "J1") (pin "1") (pinfunction "1_1") (pintype "bidirectional"))
      (node (ref "J2") (pin "10") (pinfunction "10_10") (pintype "bidirectional"))
      (node (ref "J2") (pin "12") (pinfunction "12_12") (pintype "bidirectional"))
      (node (ref "J2") (pin "14") (pinfunction "14_14") (pintype "bidirectional"))
      (node (ref "J2") (pin "16") (pinfunction "16_16") (pintype "bidirectional"))
      (node (ref "J2") (pin "19") (pinfunction "19_19") (pintype "bidirectional"))
      (node (ref "J2") (pin "2") (pinfunction "2_2") (pintype "bidirectional"))
      (node (ref "J2") (pin "21") (pinfunction "21_21") (pintype "bidirectional"))
      (node (ref "J2") (pin "24") (pinfunction "24_24") (pintype "bidirectional"))
      (node (ref "J2") (pin "4") (pinfunction "4_4") (pintype "bidirectional"))
      (node (ref "J2") (pin "6") (pinfunction "6_6") (pintype "bidirectional"))
      (node (ref "J2") (pin "8") (pinfunction "8_8") (pintype "bidirectional"))
      (node (ref "J4") (pin "A1") (pinfunction "A1_A1") (pintype "bidirectional"))
      (node (ref "J4") (pin "A12") (pinfunction "A12_A12") (pintype "bidirectional"))
      (node (ref "J4") (pin "B1") (pinfunction "B1_B1") (pintype "bidirectional"))
      (node (ref "J4") (pin "B12") (pinfunction "B12_B12") (pintype "bidirectional"))
      (node (ref "L7") (pin "2") (pinfunction "2_2") (pintype "bidirectional"))
      (node (ref "R27") (pin "2") (pinfunction "2_2") (pintype "bidirectional"))
      (node (ref "R37") (pin "1") (pinfunction "1_1") (pintype "bidirectional"))
      (node (ref "R6") (pin "1") (pinfunction "1_1") (pintype "bidirectional"))
      (node (ref "R7") (pin "1") (pinfunction "1_1") (pintype "bidirectional"))
      (node (ref "TP2") (pin "1") (pinfunction "TP1_1") (pintype "bidirectional"))
      (node (ref "U10") (pin "B3") (pinfunction "GND_B3") (pintype "input"))
      (node (ref "U11") (pin "B2") (pinfunction "GND_B2") (pintype "input"))
      (node (ref "U2") (pin "C2") (pinfunction "C2_C2") (pintype "bidirectional"))
      (node (ref "U4") (pin "5") (pinfunction "NC_5") (pintype "bidirectional"))
      (node (ref "U4") (pin "6") (pinfunction "GND_1_6") (pintype "input"))
      (node (ref "U4") (pin "7") (pinfunction "RES_7") (pintype "input"))
      (node (ref "U4") (pin "8") (pinfunction "GND_2_8") (pintype "input"))
      (node (ref "U6") (pin "B2") (pinfunction "GND_B2") (pintype "input"))
      (node (ref "U7") (pin "B2") (pinfunction "GND_B2") (pintype "input"))
      (node (ref "U8") (pin "2") (pinfunction "GND_2") (pintype "input"))
      (node (ref "U9") (pin "B3") (pinfunction "GND_B3") (pintype "input"))
    )
    (net (code "18") (name "HDK_RX0") (class "Default")
      (node (ref "J4") (pin "A11") (pinfunction "A11_A11") (pintype "bidirectional"))
      (node (ref "U9") (pin "B4") (pinfunction "COM4_B4") (pintype "input"))
    )
    (net (code "19") (name "HDK_RX1") (class "Default")
      (node (ref "J4") (pin "B11") (pinfunction "B11_B11") (pintype "bidirectional"))
      (node (ref "U10") (pin "B4") (pinfunction "COM4_B4") (pintype "input"))
    )
    (net (code "20") (name "HDK_SWDCLK0") (class "Default")
      (node (ref "J4") (pin "A2") (pinfunction "A2_A2") (pintype "bidirectional"))
      (node (ref "U9") (pin "B1") (pinfunction "COM2_B1") (pintype "input"))
    )
    (net (code "21") (name "HDK_SWDCLK1") (class "Default")
      (node (ref "J4") (pin "B2") (pinfunction "B2_B2") (pintype "bidirectional"))
      (node (ref "U10") (pin "B1") (pinfunction "COM2_B1") (pintype "input"))
    )
    (net (code "22") (name "HDK_SWDIO0") (class "Default")
      (node (ref "J4") (pin "A3") (pinfunction "A3_A3") (pintype "bidirectional"))
      (node (ref "U9") (pin "D1") (pinfunction "COM1_D1") (pintype "input"))
    )
    (net (code "23") (name "HDK_SWDIO1") (class "Default")
      (node (ref "J4") (pin "B3") (pinfunction "B3_B3") (pintype "bidirectional"))
      (node (ref "U10") (pin "D1") (pinfunction "COM1_D1") (pintype "input"))
    )
    (net (code "24") (name "HDK_TX0") (class "Default")
      (node (ref "J4") (pin "A10") (pinfunction "A10_A10") (pintype "bidirectional"))
      (node (ref "U9") (pin "A4") (pinfunction "COM3_A4") (pintype "input"))
    )
    (net (code "25") (name "HDK_TX1") (class "Default")
      (node (ref "J4") (pin "B10") (pinfunction "B10_B10") (pintype "bidirectional"))
      (node (ref "U10") (pin "A4") (pinfunction "COM3_A4") (pintype "input"))
    )
    (net (code "26") (name "HDK_VREF") (class "Default")
      (node (ref "J4") (pin "A8") (pinfunction "A8_A8") (pintype "bidirectional"))
      (node (ref "J4") (pin "B8") (pinfunction "B8_B8") (pintype "bidirectional"))
      (node (ref "U11") (pin "C1") (pinfunction "NO1_C1") (pintype "bidirectional"))
    )
    (net (code "27") (name "I2C0_SCL") (class "Default")
      (node (ref "R25") (pin "1") (pinfunction "1_1") (pintype "bidirectional"))
      (node (ref "U2") (pin "B6") (pinfunction "B6_B6") (pintype "bidirectional"))
    )
    (net (code "28") (name "I2C0_SDA") (class "Default")
      (node (ref "R24") (pin "1") (pinfunction "1_1") (pintype "bidirectional"))
      (node (ref "U2") (pin "A6") (pinfunction "A6_A6") (pintype "bidirectional"))
    )
    (net (code "29") (name "I2C1_SCL") (class "Default")
      (node (ref "J1") (pin "5") (pinfunction "5_5") (pintype "bidirectional"))
      (node (ref "R20") (pin "1") (pinfunction "1_1") (pintype "bidirectional"))
    )
    (net (code "30") (name "I2C1_SDA") (class "Default")
      (node (ref "J1") (pin "2") (pinfunction "2_2") (pintype "bidirectional"))
      (node (ref "R19") (pin "1") (pinfunction "1_1") (pintype "bidirectional"))
    )
    (net (code "31") (name "I2C2_SCL") (class "Default")
      (node (ref "R21") (pin "1") (pinfunction "1_1") (pintype "bidirectional"))
      (node (ref "R23") (pin "1") (pinfunction "1_1") (pintype "bidirectional"))
    )
    (net (code "32") (name "I2C2_SDA") (class "Default")
      (node (ref "R16") (pin "1") (pinfunction "1_1") (pintype "bidirectional"))
      (node (ref "R18") (pin "2") (pinfunction "2_2") (pintype "bidirectional"))
    )
    (net (code "33") (name "MFIO_AH") (class "Default")
      (node (ref "R26") (pin "1") (pinfunction "1_1") (pintype "bidirectional"))
    )
    (net (code "34") (name "Net-(C33-Pad2)") (class "Default")
      (node (ref "C33") (pin "2") (pinfunction "2_2") (pintype "bidirectional"))
      (node (ref "C34") (pin "2") (pinfunction "2_2") (pintype "bidirectional"))
      (node (ref "U2") (pin "A2") (pinfunction "A2_A2") (pintype "bidirectional"))
    )
    (net (code "35") (name "Net-(C37-Pad2)") (class "Default")
      (node (ref "C37") (pin "2") (pinfunction "2_2") (pintype "bidirectional"))
      (node (ref "U2") (pin "D1") (pinfunction "D1_D1") (pintype "bidirectional"))
    )
    (net (code "36") (name "Net-(C38-Pad1)") (class "Default")
      (node (ref "C38") (pin "1") (pinfunction "1_1") (pintype "bidirectional"))
      (node (ref "R37") (pin "2") (pinfunction "2_2") (pintype "bidirectional"))
    )
    (net (code "37") (name "Net-(J2-Pad1)") (class "Default")
      (node (ref "J2") (pin "1") (pinfunction "1_1") (pintype "bidirectional"))
      (node (ref "R17") (pin "1") (pinfunction "1_1") (pintype "bidirectional"))
      (node (ref "R76") (pin "2") (pinfunction "2_2") (pintype "bidirectional"))
      (node (ref "R77") (pin "1") (pinfunction "1_1") (pintype "bidirectional"))
    )
    (net (code "38") (name "Net-(J2-Pad17)") (class "Default")
      (node (ref "J2") (pin "17") (pinfunction "17_17") (pintype "bidirectional"))
      (node (ref "R18") (pin "1") (pinfunction "1_1") (pintype "bidirectional"))
    )
    (net (code "39") (name "Net-(J2-Pad18)") (class "Default")
      (node (ref "J2") (pin "18") (pinfunction "18_18") (pintype "bidirectional"))
      (node (ref "R21") (pin "2") (pinfunction "2_2") (pintype "bidirectional"))
      (node (ref "R8") (pin "2") (pinfunction "2_2") (pintype "bidirectional"))
    )
    (net (code "40") (name "Net-(J2-Pad25)") (class "Default")
      (node (ref "J2") (pin "25") (pinfunction "25_25") (pintype "bidirectional"))
      (node (ref "R78") (pin "2") (pinfunction "2_2") (pintype "bidirectional"))
      (node (ref "R79") (pin "1") (pinfunction "1_1") (pintype "bidirectional"))
    )
    (net (code "41") (name "Net-(R28-Pad2)") (class "Default")
      (node (ref "R28") (pin "2") (pinfunction "2_2") (pintype "bidirectional"))
      (node (ref "U2") (pin "A4") (pinfunction "A4_A4") (pintype "bidirectional"))
    )
    (net (code "42") (name "Net-(R29-Pad2)") (class "Default")
      (node (ref "R29") (pin "2") (pinfunction "2_2") (pintype "bidirectional"))
      (node (ref "U2") (pin "A5") (pinfunction "A5_A5") (pintype "bidirectional"))
    )
    (net (code "43") (name "Net-(R30-Pad1)") (class "Default")
      (node (ref "R30") (pin "1") (pinfunction "1_1") (pintype "bidirectional"))
      (node (ref "U2") (pin "D5") (pinfunction "D5_D5") (pintype "bidirectional"))
    )
    (net (code "44") (name "Net-(R33-Pad2)") (class "Default")
      (node (ref "R33") (pin "2") (pinfunction "2_2") (pintype "bidirectional"))
      (node (ref "U2") (pin "B4") (pinfunction "B4_B4") (pintype "bidirectional"))
    )
    (net (code "45") (name "Net-(R34-Pad2)") (class "Default")
      (node (ref "R34") (pin "2") (pinfunction "2_2") (pintype "bidirectional"))
      (node (ref "U2") (pin "B5") (pinfunction "B5_B5") (pintype "bidirectional"))
    )
    (net (code "46") (name "Net-(R35-Pad1)") (class "Default")
      (node (ref "R35") (pin "1") (pinfunction "1_1") (pintype "bidirectional"))
      (node (ref "U2") (pin "C5") (pinfunction "C5_C5") (pintype "bidirectional"))
    )
    (net (code "47") (name "Net-(R36-Pad1)") (class "Default")
      (node (ref "R36") (pin "1") (pinfunction "1_1") (pintype "bidirectional"))
      (node (ref "U2") (pin "C4") (pinfunction "C4_C4") (pintype "bidirectional"))
    )
    (net (code "48") (name "Net-(R72-Pad2)") (class "Default")
      (node (ref "R72") (pin "2") (pinfunction "2_2") (pintype "bidirectional"))
      (node (ref "U2") (pin "D4") (pinfunction "D4_D4") (pintype "bidirectional"))
    )
    (net (code "49") (name "Net-(U4-INT1)") (class "Default")
      (node (ref "R38") (pin "1") (pinfunction "1_1") (pintype "bidirectional"))
      (node (ref "R80") (pin "1") (pinfunction "1_1") (pintype "bidirectional"))
      (node (ref "U4") (pin "12") (pinfunction "INT1_12") (pintype "input"))
    )
    (net (code "50") (name "Net-(U9-NO1)") (class "Default")
      (node (ref "R39") (pin "2") (pinfunction "2_2") (pintype "bidirectional"))
      (node (ref "R40") (pin "1") (pinfunction "1_1") (pintype "bidirectional"))
      (node (ref "U9") (pin "D2") (pinfunction "NO1_D2") (pintype "output"))
    )
    (net (code "51") (name "Net-(U9-NO2)") (class "Default")
      (node (ref "R41") (pin "2") (pinfunction "2_2") (pintype "bidirectional"))
      (node (ref "R42") (pin "1") (pinfunction "1_1") (pintype "bidirectional"))
      (node (ref "U9") (pin "C1") (pinfunction "NO2_C1") (pintype "output"))
    )
    (net (code "52") (name "Net-(U11-COM1)") (class "Default")
      (node (ref "R75") (pin "1") (pinfunction "1_1") (pintype "bidirectional"))
      (node (ref "U11") (pin "B1") (pinfunction "COM1_B1") (pintype "input"))
    )
    (net (code "53") (name "RSENSE0") (class "Default")
      (node (ref "J4") (pin "A5") (pinfunction "A5_A5") (pintype "bidirectional"))
      (node (ref "R6") (pin "2") (pinfunction "2_2") (pintype "bidirectional"))
      (node (ref "U6") (pin "A2") (pinfunction "IN_A2") (pintype "input"))
    )
    (net (code "54") (name "RSENSE1") (class "Default")
      (node (ref "J4") (pin "B5") (pinfunction "B5_B5") (pintype "bidirectional"))
      (node (ref "R7") (pin "2") (pinfunction "2_2") (pintype "bidirectional"))
      (node (ref "U7") (pin "A2") (pinfunction "IN_A2") (pintype "input"))
    )
    (net (code "55") (name "RSTN_AH") (class "Default")
      (node (ref "C38") (pin "2") (pinfunction "2_2") (pintype "bidirectional"))
      (node (ref "TP11") (pin "1") (pinfunction "TP1_1") (pintype "bidirectional"))
      (node (ref "U2") (pin "C1") (pinfunction "C1_C1") (pintype "bidirectional"))
    )
    (net (code "56") (name "RTCXI") (class "Default")
      (node (ref "C57") (pin "2") (pinfunction "2_2") (pintype "bidirectional"))
      (node (ref "U2") (pin "A1") (pinfunction "A1_A1") (pintype "bidirectional"))
      (node (ref "Y3") (pin "2") (pinfunction "2_2") (pintype "bidirectional"))
    )
    (net (code "57") (name "RXD0_H") (class "Default")
      (node (ref "U9") (pin "C4") (pinfunction "NO4_C4") (pintype "output"))
    )
    (net (code "58") (name "SHIELD") (class "Default")
      (node (ref "J4") (pin "SHIELD_1") (pinfunction "SHIELD_1_SHIELD_1") (pintype "bidirectional"))
      (node (ref "J4") (pin "SHIELD_2") (pinfunction "SHIELD_2_SHIELD_2") (pintype "bidirectional"))
      (node (ref "J4") (pin "SHIELD_3") (pinfunction "SHIELD_4_SHIELD_3") (pintype "bidirectional"))
      (node (ref "J4") (pin "SHIELD_4") (pinfunction "SHIELD_3_SHIELD_4") (pintype "bidirectional"))
      (node (ref "L7") (pin "1") (pinfunction "1_1") (pintype "bidirectional"))
      (node (ref "R27") (pin "1") (pinfunction "1_1") (pintype "bidirectional"))
    )
    (net (code "59") (name "SPI0_CSACC_N") (class "Default")
      (node (ref "J2") (pin "11") (pinfunction "11_11") (pintype "bidirectional"))
      (node (ref "R31") (pin "1") (pinfunction "1_1") (pintype "bidirectional"))
      (node (ref "U4") (pin "2") (pinfunction "CS_2") (pintype "bidirectional"))
    )
    (net (code "60") (name "SPI0_CSAFE_N") (class "Default")
      (node (ref "J2") (pin "3") (pinfunction "3_3") (pintype "bidirectional"))
      (node (ref "R34") (pin "1") (pinfunction "1_1") (pintype "bidirectional"))
    )
    (net (code "61") (name "SPI0_MISO") (class "Default")
      (node (ref "J2") (pin "5") (pinfunction "5_5") (pintype "bidirectional"))
      (node (ref "R28") (pin "1") (pinfunction "1_1") (pintype "bidirectional"))
      (node (ref "U4") (pin "3") (pinfunction "SDO/SA0_3") (pintype "bidirectional"))
    )
    (net (code "62") (name "SPI0_MOSI") (class "Default")
      (node (ref "J2") (pin "9") (pinfunction "9_9") (pintype "bidirectional"))
      (node (ref "R33") (pin "1") (pinfunction "1_1") (pintype "bidirectional"))
      (node (ref "U4") (pin "4") (pinfunction "SDA/SDI/SDO_4") (pintype "bidirectional"))
    )
    (net (code "63") (name "SPI0_SCK") (class "Default")
      (node (ref "J2") (pin "7") (pinfunction "7_7") (pintype "bidirectional"))
      (node (ref "R29") (pin "1") (pinfunction "1_1") (pintype "bidirectional"))
      (node (ref "U4") (pin "1") (pinfunction "SCL/SPC_1") (pintype "bidirectional"))
    )
    (net (code "64") (name "SPI1_MISO") (class "Default")
      (node (ref "U2") (pin "C3") (pinfunction "C3_C3") (pintype "bidirectional"))
    )
    (net (code "65") (name "SPI1_MOSI") (class "Default")
      (node (ref "U2") (pin "D2") (pinfunction "D2_D2") (pintype "bidirectional"))
    )
    (net (code "66") (name "SPI1_SCK") (class "Default")
      (node (ref "U2") (pin "D3") (pinfunction "D3_D3") (pintype "bidirectional"))
    )
    (net (code "67") (name "SPI1_SS0") (class "Default")
      (node (ref "R72") (pin "1") (pinfunction "1_1") (pintype "bidirectional"))
    )
    (net (code "68") (name "SWDCLK2_H") (class "Default")
      (node (ref "R41") (pin "1") (pinfunction "1_1") (pintype "bidirectional"))
    )
    (net (code "69") (name "SWDCLK_AH") (class "Default")
      (node (ref "R4") (pin "2") (pinfunction "2_2") (pintype "bidirectional"))
      (node (ref "U10") (pin "C1") (pinfunction "NO2_C1") (pintype "output"))
    )
    (net (code "70") (name "SWDCLK_AH_P") (class "Default")
      (node (ref "R32") (pin "2") (pinfunction "2_2") (pintype "bidirectional"))
      (node (ref "R4") (pin "1") (pinfunction "1_1") (pintype "bidirectional"))
      (node (ref "R74") (pin "2") (pinfunction "2_2") (pintype "bidirectional"))
      (node (ref "TP8") (pin "1") (pinfunction "TP1_1") (pintype "bidirectional"))
      (node (ref "U2") (pin "B3") (pinfunction "B3_B3") (pintype "bidirectional"))
    )
    (net (code "71") (name "SWDCLK_H") (class "Default")
      (node (ref "R42") (pin "2") (pinfunction "2_2") (pintype "bidirectional"))
    )
    (net (code "72") (name "SWDIO2_H") (class "Default")
      (node (ref "R39") (pin "1") (pinfunction "1_1") (pintype "bidirectional"))
    )
    (net (code "73") (name "SWDIO_AH") (class "Default")
      (node (ref "R2") (pin "2") (pinfunction "2_2") (pintype "bidirectional"))
      (node (ref "U10") (pin "D2") (pinfunction "NO1_D2") (pintype "output"))
    )
    (net (code "74") (name "SWDIO_AH_P") (class "Default")
      (node (ref "R2") (pin "1") (pinfunction "1_1") (pintype "bidirectional"))
      (node (ref "R26") (pin "2") (pinfunction "2_2") (pintype "bidirectional"))
      (node (ref "TP7") (pin "1") (pinfunction "TP1_1") (pintype "bidirectional"))
      (node (ref "U2") (pin "A3") (pinfunction "A3_A3") (pintype "bidirectional"))
    )
    (net (code "75") (name "SWDIO_H") (class "Default")
      (node (ref "R40") (pin "2") (pinfunction "2_2") (pintype "bidirectional"))
    )
    (net (code "76") (name "TXD0_H") (class "Default")
      (node (ref "U9") (pin "A3") (pinfunction "NO3_A3") (pintype "output"))
    )
    (net (code "77") (name "UART0A_RX_AH") (class "Default")
      (node (ref "R3") (pin "2") (pinfunction "2_2") (pintype "bidirectional"))
      (node (ref "U10") (pin "C4") (pinfunction "NO4_C4") (pintype "output"))
    )
    (net (code "78") (name "UART0A_RX_AH_P") (class "Default")
      (node (ref "R3") (pin "1") (pinfunction "1_1") (pintype "bidirectional"))
      (node (ref "R31") (pin "2") (pinfunction "2_2") (pintype "bidirectional"))
      (node (ref "R73") (pin "2") (pinfunction "2_2") (pintype "bidirectional"))
      (node (ref "TP10") (pin "1") (pinfunction "TP1_1") (pintype "bidirectional"))
      (node (ref "U2") (pin "D6") (pinfunction "D6_D6") (pintype "bidirectional"))
    )
    (net (code "79") (name "UART0A_TX_AH") (class "Default")
      (node (ref "R11") (pin "1") (pinfunction "1_1") (pintype "bidirectional"))
      (node (ref "U10") (pin "A3") (pinfunction "NO3_A3") (pintype "output"))
    )
    (net (code "80") (name "UART0A_TX_AH_P") (class "Default")
      (node (ref "R11") (pin "2") (pinfunction "2_2") (pintype "bidirectional"))
      (node (ref "R12") (pin "2") (pinfunction "2_2") (pintype "bidirectional"))
      (node (ref "TP9") (pin "1") (pinfunction "TP1_1") (pintype "bidirectional"))
      (node (ref "U2") (pin "C6") (pinfunction "C6_C6") (pintype "bidirectional"))
    )
    (net (code "81") (name "USB_DM") (class "Default")
      (node (ref "R9") (pin "2") (pinfunction "2_2") (pintype "bidirectional"))
    )
    (net (code "82") (name "USB_DP") (class "Default")
      (node (ref "R10") (pin "2") (pinfunction "2_2") (pintype "bidirectional"))
    )
    (net (code "83") (name "USB_VBUS") (class "Default")
      (node (ref "C56") (pin "2") (pinfunction "2_2") (pintype "bidirectional"))
      (node (ref "C66") (pin "2") (pinfunction "2_2") (pintype "bidirectional"))
      (node (ref "L8") (pin "2") (pinfunction "2_2") (pintype "bidirectional"))
    )
    (net (code "84") (name "USB_VBUS_C") (class "Default")
      (node (ref "C67") (pin "2") (pinfunction "2_2") (pintype "bidirectional"))
      (node (ref "J4") (pin "A4") (pinfunction "A4_A4") (pintype "bidirectional"))
      (node (ref "J4") (pin "B4") (pinfunction "B4_B4") (pintype "bidirectional"))
      (node (ref "L8") (pin "1") (pinfunction "1_1") (pintype "bidirectional"))
      (node (ref "U8") (pin "5") (pinfunction "VCC_5") (pintype "bidirectional"))
    )
    (net (code "85") (name "VREGO_A") (class "Default")
      (node (ref "R19") (pin "2") (pinfunction "2_2") (pintype "bidirectional"))
      (node (ref "R20") (pin "2") (pinfunction "2_2") (pintype "bidirectional"))
      (node (ref "R75") (pin "2") (pinfunction "2_2") (pintype "bidirectional"))
    )
    (net (code "86") (name "unconnected-(J4-PadA9)") (class "Default")
      (node (ref "J4") (pin "A9") (pinfunction "A9_A9") (pintype "bidirectional"))
    )
    (net (code "87") (name "unconnected-(J4-PadB9)") (class "Default")
      (node (ref "J4") (pin "B9") (pinfunction "B9_B9") (pintype "bidirectional"))
    )
    (net (code "88") (name "unconnected-(U8-NC1-Pad3)") (class "Default")
      (node (ref "U8") (pin "3") (pinfunction "NC1_3") (pintype "bidirectional"))
    )
    (net (code "89") (name "unconnected-(U8-NC2-Pad6)") (class "Default")
      (node (ref "U8") (pin "6") (pinfunction "NC2_6") (pintype "bidirectional"))
    )
    (net (code "90") (name "unconnected-(U11-COM2-PadB3)") (class "Default")
      (node (ref "U11") (pin "B3") (pinfunction "COM2_B3") (pintype "input"))
    )
    (net (code "91") (name "unconnected-(U11-NC1-PadA1)") (class "Default")
      (node (ref "U11") (pin "A1") (pinfunction "NC1_A1") (pintype "bidirectional"))
    )
    (net (code "92") (name "unconnected-(U11-NC2-PadA3)") (class "Default")
      (node (ref "U11") (pin "A3") (pinfunction "NC2_A3") (pintype "bidirectional"))
    )
    (net (code "93") (name "unconnected-(U11-NO2-PadC3)") (class "Default")
      (node (ref "U11") (pin "C3") (pinfunction "NO2_C3") (pintype "bidirectional"))
    )
  )
)
